# 82230KPC-1-K-1V0-241216.net
KiCad netlist of a schematic drawn in Altium Designer
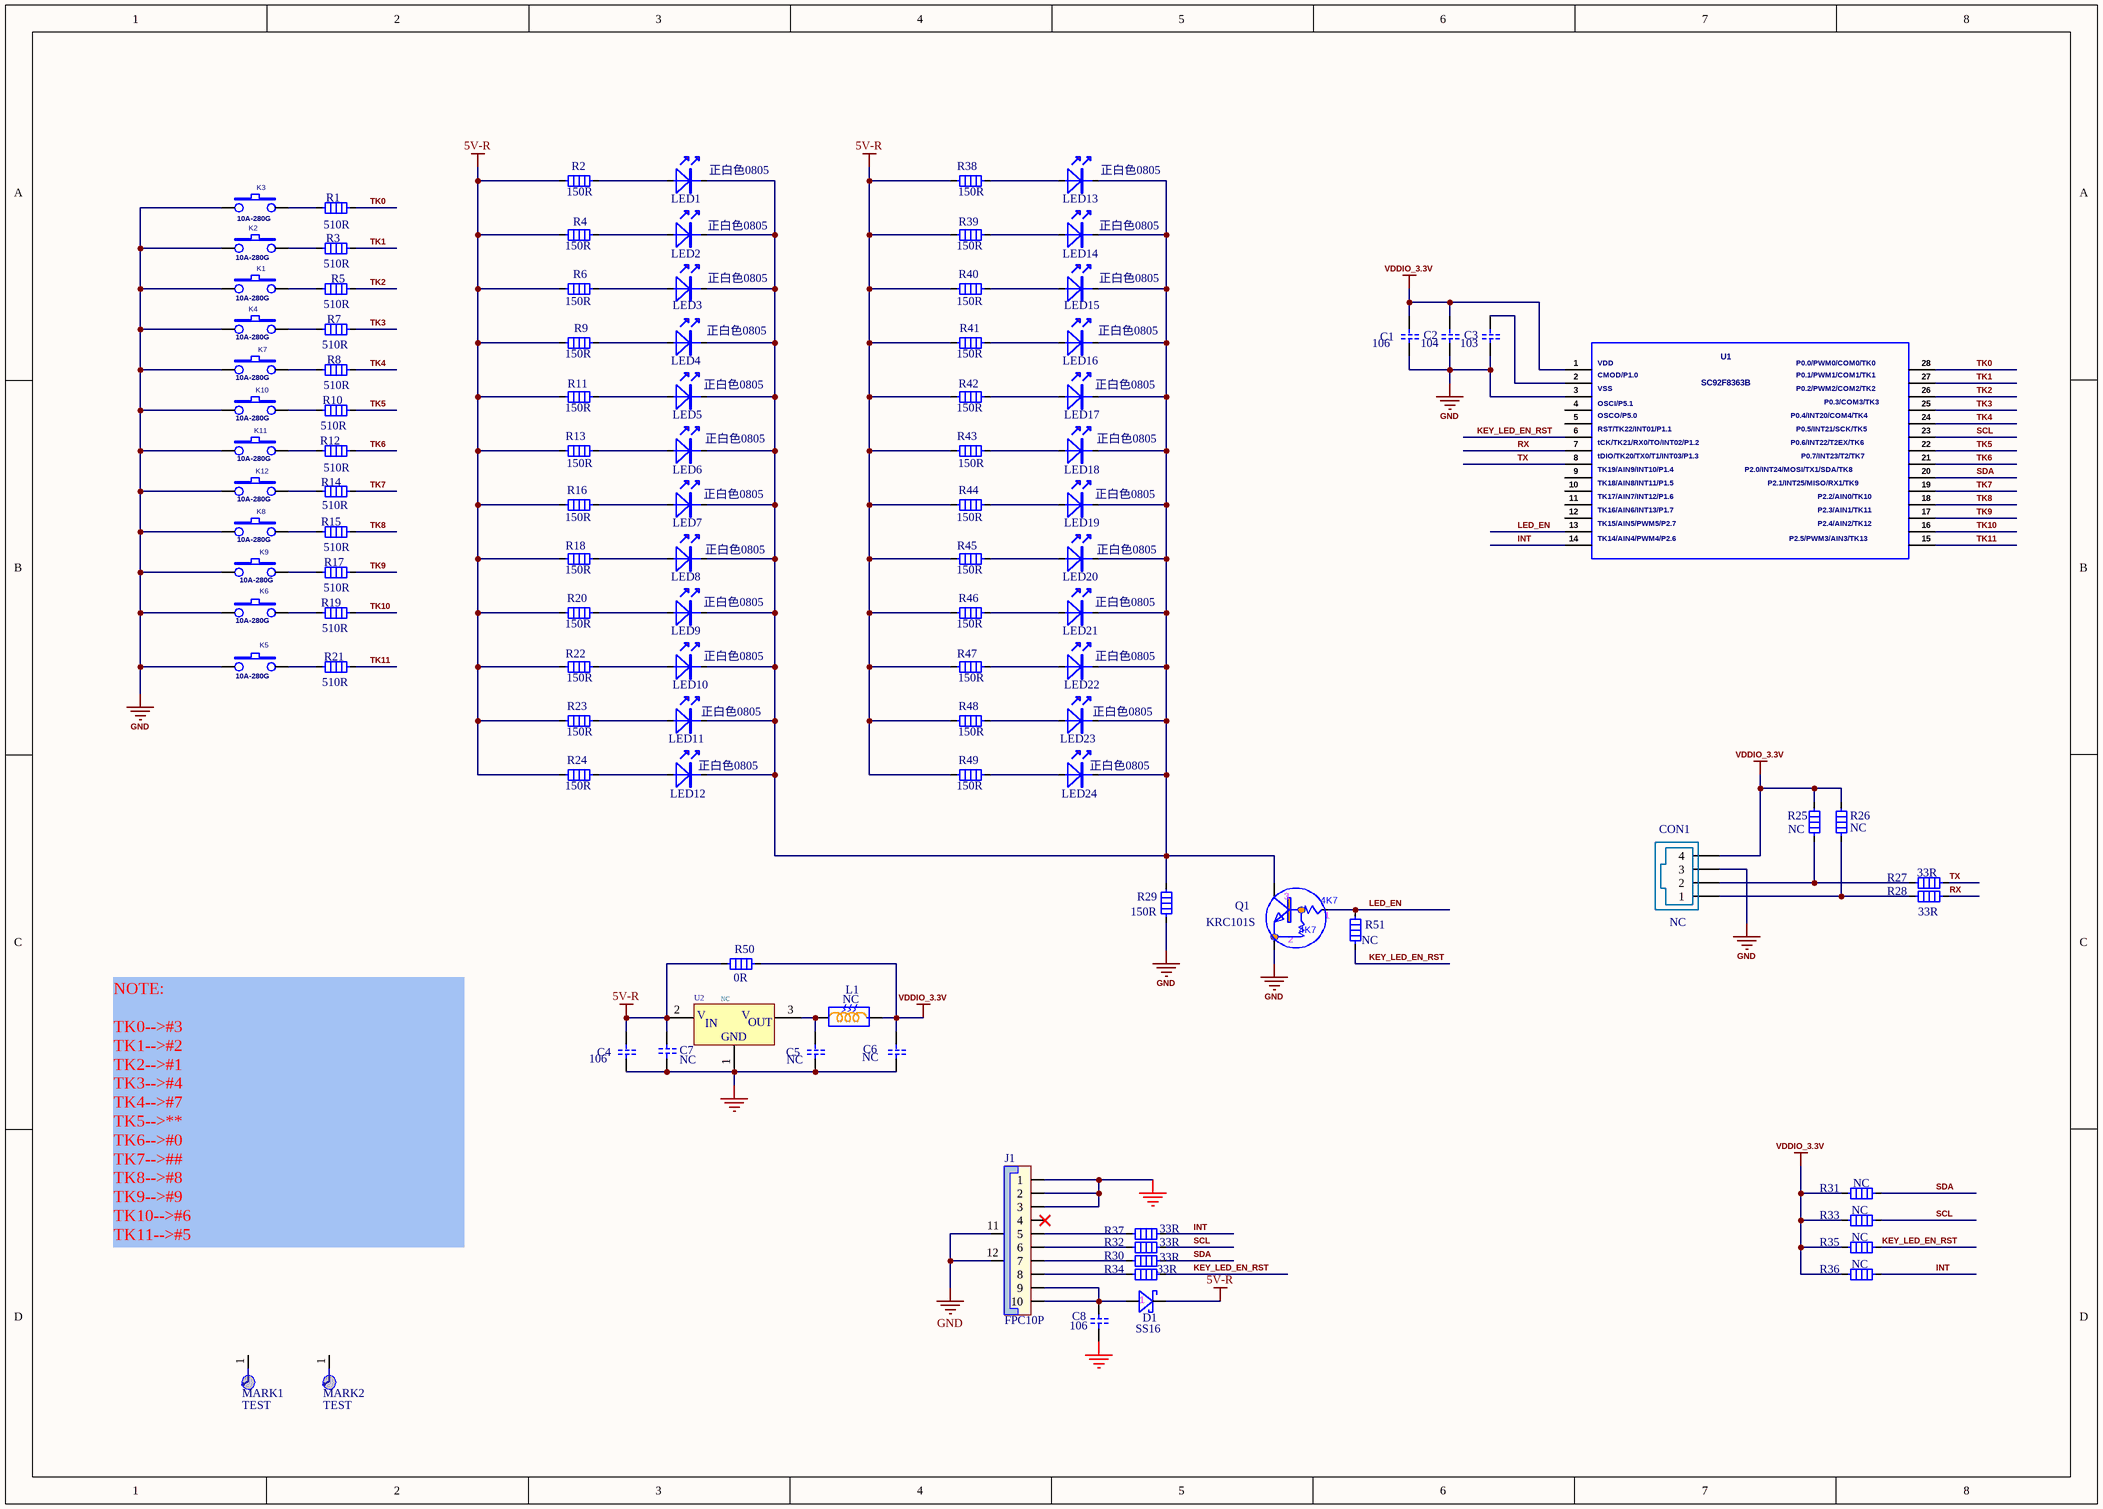
[diagram p0: 82230KPC-1-K-1V0-241216.SchDoc]

(export (version "E")
  (design (tool "Eeschema 10.0.6"))
  (components
    (comp (ref "C1")
      (value "106")
      (footprint "C0603-Z")
      (description "电容器，0603贴片，106, 6V3 精度20%")
      (libsource (lib "Dbdevice") (part "CAP_0603"))
    )
    (comp (ref "C2")
      (value "104")
      (footprint "C0603-Z")
      (description "电容器，0603贴片，104, 50V 精度10%")
      (libsource (lib "Dbdevice") (part "CAP_0603"))
    )
    (comp (ref "C3")
      (value "103")
      (footprint "C0603-Z")
      (description "电容器，0603贴片，103, 50V 精度10%")
      (libsource (lib "Dbdevice") (part "CAP_0603"))
    )
    (comp (ref "C4")
      (value "106")
      (footprint "C0603-Z")
      (description "电容器，0603贴片，106, 6V3 精度20%")
      (libsource (lib "Dbdevice") (part "CAP_0603"))
    )
    (comp (ref "C5")
      (value "NC")
      (footprint "C0603-Z")
      (description "电容器，0603贴片，106, 6V3 精度20%")
      (libsource (lib "Dbdevice") (part "CAP_0603"))
    )
    (comp (ref "C6")
      (value "NC")
      (footprint "C0603-Z")
      (description "电容器，0603贴片，106, 6V3 精度20%")
      (libsource (lib "Dbdevice") (part "CAP_0603"))
    )
    (comp (ref "C7")
      (value "NC")
      (footprint "C0603-Z")
      (description "电容器，0603贴片，104, 50V 精度10%")
      (libsource (lib "Dbdevice") (part "CAP_0603"))
    )
    (comp (ref "C8")
      (value "106")
      (footprint "C0603-Z")
      (description "电容器，0603贴片，106, 6V3 精度20%")
      (libsource (lib "Dbdevice") (part "CAP_0603"))
    )
    (comp (ref "CON1")
      (value "NC")
      (footprint "PH4P2.0_VS-Z")
      (description "4PIN直插插座（银针外露2.5mm，数据参考看上方物料图片）,4PIN插座 脚距2.0mm 插座180°米色耐高温  SCD2001AZ-104139")
      (libsource (lib "Dbdevice") (part "DIP4P"))
    )
    (comp (ref "D1")
      (value "SS16")
      (footprint "SMAF-Z")
      (description "贴片肖特基二极管，SMAF SS16（印字SS16）")
      (libsource (lib "Dbdevice") (part "DST"))
    )
    (comp (ref "J1")
      (value "FPC10P")
      (footprint "FPC10_0.5-Z")
      (description "FPC连接器 软排线插座 间距0.5mm 10P 下接触 卧贴翻盖式 (卓誉佳）（编带式）")
      (libsource (lib "Dbdevice") (part "FPC10P"))
    )
    (comp (ref "K1")
      (value "10A-280G")
      (footprint "SD-9X9-S")
      (description "锅仔片")
      (libsource (lib "*") (part "KEY_4P_SMD_6X6MM"))
    )
    (comp (ref "K2")
      (value "10A-280G")
      (footprint "SD-9X9-S")
      (description "锅仔片")
      (libsource (lib "*") (part "KEY_4P_SMD_6X6MM"))
    )
    (comp (ref "K3")
      (value "10A-280G")
      (footprint "SD-9X9-S")
      (description "锅仔片")
      (libsource (lib "*") (part "KEY_4P_SMD_6X6MM"))
    )
    (comp (ref "K4")
      (value "10A-280G")
      (footprint "SD-9X9-S")
      (description "锅仔片")
      (libsource (lib "*") (part "KEY_4P_SMD_6X6MM"))
    )
    (comp (ref "K5")
      (value "10A-280G")
      (footprint "SD-9X9-S")
      (description "锅仔片")
      (libsource (lib "*") (part "KEY_4P_SMD_6X6MM"))
    )
    (comp (ref "K6")
      (value "10A-280G")
      (footprint "SD-9X9-S")
      (description "锅仔片")
      (libsource (lib "*") (part "KEY_4P_SMD_6X6MM"))
    )
    (comp (ref "K7")
      (value "10A-280G")
      (footprint "SD-9X9-S")
      (description "锅仔片")
      (libsource (lib "*") (part "KEY_4P_SMD_6X6MM"))
    )
    (comp (ref "K8")
      (value "10A-280G")
      (footprint "SD-9X9-S")
      (description "锅仔片")
      (libsource (lib "*") (part "KEY_4P_SMD_6X6MM"))
    )
    (comp (ref "K9")
      (value "10A-280G")
      (footprint "SD-9X9-S")
      (description "锅仔片")
      (libsource (lib "*") (part "KEY_4P_SMD_6X6MM"))
    )
    (comp (ref "K10")
      (value "10A-280G")
      (footprint "SD-9X9-S")
      (description "锅仔片")
      (libsource (lib "*") (part "KEY_4P_SMD_6X6MM"))
    )
    (comp (ref "K11")
      (value "10A-280G")
      (footprint "SD-9X9-S")
      (description "锅仔片")
      (libsource (lib "*") (part "KEY_4P_SMD_6X6MM"))
    )
    (comp (ref "K12")
      (value "10A-280G")
      (footprint "SD-9X9-S")
      (description "锅仔片")
      (libsource (lib "*") (part "KEY_4P_SMD_6X6MM"))
    )
    (comp (ref "L1")
      (value "NC")
      (footprint "L0805-Z")
      (description "磁珠 0805贴片 2.5A 220ohm@100MHZ DCR=0.050")
      (libsource (lib "Dbdevice") (part "LFB"))
    )
    (comp (ref "LED1")
      (value "正白色0805")
      (footprint "LED0805AK-X")
      (description "贴片发光二极管, 0805贴片LED 正白色 发光二极管")
      (libsource (lib "Dbdevice") (part "LED_12"))
    )
    (comp (ref "LED2")
      (value "正白色0805")
      (footprint "LED0805AK-X")
      (description "贴片发光二极管, 0805贴片LED 正白色 发光二极管")
      (libsource (lib "Dbdevice") (part "LED_12"))
    )
    (comp (ref "LED3")
      (value "正白色0805")
      (footprint "LED0805AK-X")
      (description "贴片发光二极管, 0805贴片LED 正白色 发光二极管")
      (libsource (lib "Dbdevice") (part "LED_12"))
    )
    (comp (ref "LED4")
      (value "正白色0805")
      (footprint "LED0805AK-X")
      (description "贴片发光二极管, 0805贴片LED 正白色 发光二极管")
      (libsource (lib "Dbdevice") (part "LED_12"))
    )
    (comp (ref "LED5")
      (value "正白色0805")
      (footprint "LED0805AK-X")
      (description "贴片发光二极管, 0805贴片LED 正白色 发光二极管")
      (libsource (lib "Dbdevice") (part "LED_12"))
    )
    (comp (ref "LED6")
      (value "正白色0805")
      (footprint "LED0805AK-X")
      (description "贴片发光二极管, 0805贴片LED 正白色 发光二极管")
      (libsource (lib "Dbdevice") (part "LED_12"))
    )
    (comp (ref "LED7")
      (value "正白色0805")
      (footprint "LED0805AK-X")
      (description "贴片发光二极管, 0805贴片LED 正白色 发光二极管")
      (libsource (lib "Dbdevice") (part "LED_12"))
    )
    (comp (ref "LED8")
      (value "正白色0805")
      (footprint "LED0805AK-X")
      (description "贴片发光二极管, 0805贴片LED 正白色 发光二极管")
      (libsource (lib "Dbdevice") (part "LED_12"))
    )
    (comp (ref "LED9")
      (value "正白色0805")
      (footprint "LED0805AK-X")
      (description "贴片发光二极管, 0805贴片LED 正白色 发光二极管")
      (libsource (lib "Dbdevice") (part "LED_12"))
    )
    (comp (ref "LED10")
      (value "正白色0805")
      (footprint "LED0805AK-X")
      (description "贴片发光二极管, 0805贴片LED 正白色 发光二极管")
      (libsource (lib "Dbdevice") (part "LED_12"))
    )
    (comp (ref "LED11")
      (value "正白色0805")
      (footprint "LED0805AK-X")
      (description "贴片发光二极管, 0805贴片LED 正白色 发光二极管")
      (libsource (lib "Dbdevice") (part "LED_12"))
    )
    (comp (ref "LED12")
      (value "正白色0805")
      (footprint "LED0805AK-X")
      (description "贴片发光二极管, 0805贴片LED 正白色 发光二极管")
      (libsource (lib "Dbdevice") (part "LED_12"))
    )
    (comp (ref "LED13")
      (value "正白色0805")
      (footprint "LED0805AK-X")
      (description "贴片发光二极管, 0805贴片LED 正白色 发光二极管")
      (libsource (lib "Dbdevice") (part "LED_12"))
    )
    (comp (ref "LED14")
      (value "正白色0805")
      (footprint "LED0805AK-X")
      (description "贴片发光二极管, 0805贴片LED 正白色 发光二极管")
      (libsource (lib "Dbdevice") (part "LED_12"))
    )
    (comp (ref "LED15")
      (value "正白色0805")
      (footprint "LED0805AK-X")
      (description "贴片发光二极管, 0805贴片LED 正白色 发光二极管")
      (libsource (lib "Dbdevice") (part "LED_12"))
    )
    (comp (ref "LED16")
      (value "正白色0805")
      (footprint "LED0805AK-X")
      (description "贴片发光二极管, 0805贴片LED 正白色 发光二极管")
      (libsource (lib "Dbdevice") (part "LED_12"))
    )
    (comp (ref "LED17")
      (value "正白色0805")
      (footprint "LED0805AK-X")
      (description "贴片发光二极管, 0805贴片LED 正白色 发光二极管")
      (libsource (lib "Dbdevice") (part "LED_12"))
    )
    (comp (ref "LED18")
      (value "正白色0805")
      (footprint "LED0805AK-X")
      (description "贴片发光二极管, 0805贴片LED 正白色 发光二极管")
      (libsource (lib "Dbdevice") (part "LED_12"))
    )
    (comp (ref "LED19")
      (value "正白色0805")
      (footprint "LED0805AK-X")
      (description "贴片发光二极管, 0805贴片LED 正白色 发光二极管")
      (libsource (lib "Dbdevice") (part "LED_12"))
    )
    (comp (ref "LED20")
      (value "正白色0805")
      (footprint "LED0805AK-X")
      (description "贴片发光二极管, 0805贴片LED 正白色 发光二极管")
      (libsource (lib "Dbdevice") (part "LED_12"))
    )
    (comp (ref "LED21")
      (value "正白色0805")
      (footprint "LED0805AK-X")
      (description "贴片发光二极管, 0805贴片LED 正白色 发光二极管")
      (libsource (lib "Dbdevice") (part "LED_12"))
    )
    (comp (ref "LED22")
      (value "正白色0805")
      (footprint "LED0805AK-X")
      (description "贴片发光二极管, 0805贴片LED 正白色 发光二极管")
      (libsource (lib "Dbdevice") (part "LED_12"))
    )
    (comp (ref "LED23")
      (value "正白色0805")
      (footprint "LED0805AK-X")
      (description "贴片发光二极管, 0805贴片LED 正白色 发光二极管")
      (libsource (lib "Dbdevice") (part "LED_12"))
    )
    (comp (ref "LED24")
      (value "正白色0805")
      (footprint "LED0805AK-X")
      (description "贴片发光二极管, 0805贴片LED 正白色 发光二极管")
      (libsource (lib "Dbdevice") (part "LED_12"))
    )
    (comp (ref "MARK1") (value "TEST") (footprint "MARK1") (libsource (lib "*") (part "TEST")))
    (comp (ref "MARK2") (value "TEST") (footprint "MARK1") (libsource (lib "*") (part "TEST")))
    (comp (ref "Q1")
      (value "KRC101S")
      (footprint "SOT23_Z")
      (description "贴片三极管，KRC101S  SOT-23 NPN型带阻三极管")
      (libsource (lib "Dbdevice") (part "NPN_R_1"))
    )
    (comp (ref "R1")
      (value "510R")
      (footprint "R0603-Z")
      (description "电阻器，0603贴片，510R,精度5%")
      (libsource (lib "Dbdevice") (part "RES_0603"))
    )
    (comp (ref "R2")
      (value "150R")
      (footprint "R0603-Z")
      (description "电阻器，0603贴片，150R,精度5%")
      (libsource (lib "Dbdevice") (part "RES_0603"))
    )
    (comp (ref "R3")
      (value "510R")
      (footprint "R0603-Z")
      (description "电阻器，0603贴片，510R,精度5%")
      (libsource (lib "Dbdevice") (part "RES_0603"))
    )
    (comp (ref "R4")
      (value "150R")
      (footprint "R0603-Z")
      (description "电阻器，0603贴片，150R,精度5%")
      (libsource (lib "Dbdevice") (part "RES_0603"))
    )
    (comp (ref "R5")
      (value "510R")
      (footprint "R0603-Z")
      (description "电阻器，0603贴片，510R,精度5%")
      (libsource (lib "Dbdevice") (part "RES_0603"))
    )
    (comp (ref "R6")
      (value "150R")
      (footprint "R0603-Z")
      (description "电阻器，0603贴片，150R,精度5%")
      (libsource (lib "Dbdevice") (part "RES_0603"))
    )
    (comp (ref "R7")
      (value "510R")
      (footprint "R0603-Z")
      (description "电阻器，0603贴片，510R,精度5%")
      (libsource (lib "Dbdevice") (part "RES_0603"))
    )
    (comp (ref "R8")
      (value "510R")
      (footprint "R0603-Z")
      (description "电阻器，0603贴片，510R,精度5%")
      (libsource (lib "Dbdevice") (part "RES_0603"))
    )
    (comp (ref "R9")
      (value "150R")
      (footprint "R0603-Z")
      (description "电阻器，0603贴片，150R,精度5%")
      (libsource (lib "Dbdevice") (part "RES_0603"))
    )
    (comp (ref "R10")
      (value "510R")
      (footprint "R0603-Z")
      (description "电阻器，0603贴片，510R,精度5%")
      (libsource (lib "Dbdevice") (part "RES_0603"))
    )
    (comp (ref "R11")
      (value "150R")
      (footprint "R0603-Z")
      (description "电阻器，0603贴片，150R,精度5%")
      (libsource (lib "Dbdevice") (part "RES_0603"))
    )
    (comp (ref "R12")
      (value "510R")
      (footprint "R0603-Z")
      (description "电阻器，0603贴片，510R,精度5%")
      (libsource (lib "Dbdevice") (part "RES_0603"))
    )
    (comp (ref "R13")
      (value "150R")
      (footprint "R0603-Z")
      (description "电阻器，0603贴片，150R,精度5%")
      (libsource (lib "Dbdevice") (part "RES_0603"))
    )
    (comp (ref "R14")
      (value "510R")
      (footprint "R0603-Z")
      (description "电阻器，0603贴片，510R,精度5%")
      (libsource (lib "Dbdevice") (part "RES_0603"))
    )
    (comp (ref "R15")
      (value "510R")
      (footprint "R0603-Z")
      (description "电阻器，0603贴片，510R,精度5%")
      (libsource (lib "Dbdevice") (part "RES_0603"))
    )
    (comp (ref "R16")
      (value "150R")
      (footprint "R0603-Z")
      (description "电阻器，0603贴片，150R,精度5%")
      (libsource (lib "Dbdevice") (part "RES_0603"))
    )
    (comp (ref "R17")
      (value "510R")
      (footprint "R0603-Z")
      (description "电阻器，0603贴片，510R,精度5%")
      (libsource (lib "Dbdevice") (part "RES_0603"))
    )
    (comp (ref "R18")
      (value "150R")
      (footprint "R0603-Z")
      (description "电阻器，0603贴片，150R,精度5%")
      (libsource (lib "Dbdevice") (part "RES_0603"))
    )
    (comp (ref "R19")
      (value "510R")
      (footprint "R0603-Z")
      (description "电阻器，0603贴片，510R,精度5%")
      (libsource (lib "Dbdevice") (part "RES_0603"))
    )
    (comp (ref "R20")
      (value "150R")
      (footprint "R0603-Z")
      (description "电阻器，0603贴片，150R,精度5%")
      (libsource (lib "Dbdevice") (part "RES_0603"))
    )
    (comp (ref "R21")
      (value "510R")
      (footprint "R0603-Z")
      (description "电阻器，0603贴片，510R,精度5%")
      (libsource (lib "Dbdevice") (part "RES_0603"))
    )
    (comp (ref "R22")
      (value "150R")
      (footprint "R0603-Z")
      (description "电阻器，0603贴片，150R,精度5%")
      (libsource (lib "Dbdevice") (part "RES_0603"))
    )
    (comp (ref "R23")
      (value "150R")
      (footprint "R0603-Z")
      (description "电阻器，0603贴片，150R,精度5%")
      (libsource (lib "Dbdevice") (part "RES_0603"))
    )
    (comp (ref "R24")
      (value "150R")
      (footprint "R0603-Z")
      (description "电阻器，0603贴片，150R,精度5%")
      (libsource (lib "Dbdevice") (part "RES_0603"))
    )
    (comp (ref "R25")
      (value "NC")
      (footprint "R0603-Z")
      (description "电阻器，0603贴片，10K,精度5%")
      (libsource (lib "Dbdevice") (part "RES_0603"))
    )
    (comp (ref "R26")
      (value "NC")
      (footprint "R0603-Z")
      (description "电阻器，0603贴片，10K,精度5%")
      (libsource (lib "Dbdevice") (part "RES_0603"))
    )
    (comp (ref "R27")
      (value "33R")
      (footprint "R0603-Z")
      (description "电阻器，0603贴片，33R,精度5%")
      (libsource (lib "Dbdevice") (part "RES_0603"))
    )
    (comp (ref "R28")
      (value "33R")
      (footprint "R0603-Z")
      (description "电阻器，0603贴片，33R,精度5%")
      (libsource (lib "Dbdevice") (part "RES_0603"))
    )
    (comp (ref "R29")
      (value "150R")
      (footprint "R0603-Z")
      (description "电阻器，0603贴片，150R,精度5%")
      (libsource (lib "Dbdevice") (part "RES_0603"))
    )
    (comp (ref "R30")
      (value "33R")
      (footprint "R0603-Z")
      (description "电阻器，0603贴片，33R,精度5%")
      (libsource (lib "Dbdevice") (part "RES_0603"))
    )
    (comp (ref "R31")
      (value "NC")
      (footprint "R0603-Z")
      (description "电阻器，0603贴片，10K,精度5%")
      (libsource (lib "Dbdevice") (part "RES_0603"))
    )
    (comp (ref "R32")
      (value "33R")
      (footprint "R0603-Z")
      (description "电阻器，0603贴片，33R,精度5%")
      (libsource (lib "Dbdevice") (part "RES_0603"))
    )
    (comp (ref "R33")
      (value "NC")
      (footprint "R0603-Z")
      (description "电阻器，0603贴片，10K,精度5%")
      (libsource (lib "Dbdevice") (part "RES_0603"))
    )
    (comp (ref "R34")
      (value "33R")
      (footprint "R0603-Z")
      (description "电阻器，0603贴片，33R,精度5%")
      (libsource (lib "Dbdevice") (part "RES_0603"))
    )
    (comp (ref "R35")
      (value "NC")
      (footprint "R0603-Z")
      (description "电阻器，0603贴片，10K,精度5%")
      (libsource (lib "Dbdevice") (part "RES_0603"))
    )
    (comp (ref "R36")
      (value "NC")
      (footprint "R0603-Z")
      (description "电阻器，0603贴片，10K,精度5%")
      (libsource (lib "Dbdevice") (part "RES_0603"))
    )
    (comp (ref "R37")
      (value "33R")
      (footprint "R0603-Z")
      (description "电阻器，0603贴片，33R,精度5%")
      (libsource (lib "Dbdevice") (part "RES_0603"))
    )
    (comp (ref "R38")
      (value "150R")
      (footprint "R0603-Z")
      (description "电阻器，0603贴片，150R,精度5%")
      (libsource (lib "Dbdevice") (part "RES_0603"))
    )
    (comp (ref "R39")
      (value "150R")
      (footprint "R0603-Z")
      (description "电阻器，0603贴片，150R,精度5%")
      (libsource (lib "Dbdevice") (part "RES_0603"))
    )
    (comp (ref "R40")
      (value "150R")
      (footprint "R0603-Z")
      (description "电阻器，0603贴片，150R,精度5%")
      (libsource (lib "Dbdevice") (part "RES_0603"))
    )
    (comp (ref "R41")
      (value "150R")
      (footprint "R0603-Z")
      (description "电阻器，0603贴片，150R,精度5%")
      (libsource (lib "Dbdevice") (part "RES_0603"))
    )
    (comp (ref "R42")
      (value "150R")
      (footprint "R0603-Z")
      (description "电阻器，0603贴片，150R,精度5%")
      (libsource (lib "Dbdevice") (part "RES_0603"))
    )
    (comp (ref "R43")
      (value "150R")
      (footprint "R0603-Z")
      (description "电阻器，0603贴片，150R,精度5%")
      (libsource (lib "Dbdevice") (part "RES_0603"))
    )
    (comp (ref "R44")
      (value "150R")
      (footprint "R0603-Z")
      (description "电阻器，0603贴片，150R,精度5%")
      (libsource (lib "Dbdevice") (part "RES_0603"))
    )
    (comp (ref "R45")
      (value "150R")
      (footprint "R0603-Z")
      (description "电阻器，0603贴片，150R,精度5%")
      (libsource (lib "Dbdevice") (part "RES_0603"))
    )
    (comp (ref "R46")
      (value "150R")
      (footprint "R0603-Z")
      (description "电阻器，0603贴片，150R,精度5%")
      (libsource (lib "Dbdevice") (part "RES_0603"))
    )
    (comp (ref "R47")
      (value "150R")
      (footprint "R0603-Z")
      (description "电阻器，0603贴片，150R,精度5%")
      (libsource (lib "Dbdevice") (part "RES_0603"))
    )
    (comp (ref "R48")
      (value "150R")
      (footprint "R0603-Z")
      (description "电阻器，0603贴片，150R,精度5%")
      (libsource (lib "Dbdevice") (part "RES_0603"))
    )
    (comp (ref "R49")
      (value "150R")
      (footprint "R0603-Z")
      (description "电阻器，0603贴片，150R,精度5%")
      (libsource (lib "Dbdevice") (part "RES_0603"))
    )
    (comp (ref "R50")
      (value "0R")
      (footprint "R0603-Z")
      (description "电阻器，0603贴片，0R,精度5%")
      (libsource (lib "Dbdevice") (part "RES_0603"))
    )
    (comp (ref "R51")
      (value "NC")
      (footprint "R0603-Z")
      (description "电阻器，0603贴片，0R,精度5%")
      (libsource (lib "Dbdevice") (part "RES_0603"))
    )
    (comp (ref "U1") (value "SC92F8363B") (footprint "SSOP28-Z") (libsource (lib "*") (part "SC92F8363B")))
    (comp (ref "U2")
      (value "NC")
      (footprint "SOT-89-Z")
      (description "三端稳压器，三端稳压器HT7533 电流100mA SOT-89")
      (libsource (lib "*") (part "7905"))
    )
  )
  (nets
    (net (code "1") (name "/INT") (class "Default")
      (node (ref "R36") (pin "1") (pintype "passive"))
      (node (ref "R37") (pin "1") (pintype "passive"))
      (node (ref "U1") (pin "14") (pinfunction "14_14") (pintype "passive"))
    )
    (net (code "2") (name "/KEY_LED_EN_RST") (class "Default")
      (node (ref "R34") (pin "1") (pintype "passive"))
      (node (ref "R35") (pin "1") (pintype "passive"))
      (node (ref "R51") (pin "1") (pintype "passive"))
      (node (ref "U1") (pin "6") (pinfunction "6_6") (pintype "passive"))
    )
    (net (code "3") (name "/LED_EN") (class "Default")
      (node (ref "Q1") (pin "1") (pinfunction "B_1") (pintype "passive"))
      (node (ref "R51") (pin "2") (pintype "passive"))
      (node (ref "U1") (pin "13") (pinfunction "13_13") (pintype "passive"))
    )
    (net (code "4") (name "/RX") (class "Default")
      (node (ref "R28") (pin "1") (pintype "passive"))
      (node (ref "U1") (pin "7") (pinfunction "7_7") (pintype "passive"))
    )
    (net (code "5") (name "/SCL") (class "Default")
      (node (ref "R32") (pin "1") (pintype "passive"))
      (node (ref "R33") (pin "1") (pintype "passive"))
      (node (ref "U1") (pin "23") (pinfunction "23_23") (pintype "passive"))
    )
    (net (code "6") (name "/SDA") (class "Default")
      (node (ref "R30") (pin "1") (pintype "passive"))
      (node (ref "R31") (pin "1") (pintype "passive"))
      (node (ref "U1") (pin "20") (pinfunction "20_20") (pintype "passive"))
    )
    (net (code "7") (name "/TK0") (class "Default")
      (node (ref "R1") (pin "1") (pintype "passive"))
      (node (ref "U1") (pin "28") (pinfunction "28_28") (pintype "passive"))
    )
    (net (code "8") (name "/TK1") (class "Default")
      (node (ref "R3") (pin "1") (pintype "passive"))
      (node (ref "U1") (pin "27") (pinfunction "27_27") (pintype "passive"))
    )
    (net (code "9") (name "/TK2") (class "Default")
      (node (ref "R5") (pin "1") (pintype "passive"))
      (node (ref "U1") (pin "26") (pinfunction "26_26") (pintype "passive"))
    )
    (net (code "10") (name "/TK3") (class "Default")
      (node (ref "R7") (pin "1") (pintype "passive"))
      (node (ref "U1") (pin "25") (pinfunction "25_25") (pintype "passive"))
    )
    (net (code "11") (name "/TK4") (class "Default")
      (node (ref "R8") (pin "1") (pintype "passive"))
      (node (ref "U1") (pin "24") (pinfunction "24_24") (pintype "passive"))
    )
    (net (code "12") (name "/TK5") (class "Default")
      (node (ref "R10") (pin "1") (pintype "passive"))
      (node (ref "U1") (pin "22") (pinfunction "22_22") (pintype "passive"))
    )
    (net (code "13") (name "/TK6") (class "Default")
      (node (ref "R12") (pin "1") (pintype "passive"))
      (node (ref "U1") (pin "21") (pinfunction "21_21") (pintype "passive"))
    )
    (net (code "14") (name "/TK7") (class "Default")
      (node (ref "R14") (pin "1") (pintype "passive"))
      (node (ref "U1") (pin "19") (pinfunction "19_19") (pintype "passive"))
    )
    (net (code "15") (name "/TK8") (class "Default")
      (node (ref "R15") (pin "1") (pintype "passive"))
      (node (ref "U1") (pin "18") (pinfunction "18_18") (pintype "passive"))
    )
    (net (code "16") (name "/TK9") (class "Default")
      (node (ref "R17") (pin "1") (pintype "passive"))
      (node (ref "U1") (pin "17") (pinfunction "17_17") (pintype "passive"))
    )
    (net (code "17") (name "/TK10") (class "Default")
      (node (ref "R19") (pin "1") (pintype "passive"))
      (node (ref "U1") (pin "16") (pinfunction "16_16") (pintype "passive"))
    )
    (net (code "18") (name "/TK11") (class "Default")
      (node (ref "R21") (pin "1") (pintype "passive"))
      (node (ref "U1") (pin "15") (pinfunction "15_15") (pintype "passive"))
    )
    (net (code "19") (name "/TX") (class "Default")
      (node (ref "R27") (pin "1") (pintype "passive"))
      (node (ref "U1") (pin "8") (pinfunction "8_8") (pintype "passive"))
    )
    (net (code "20") (name "5V-R") (class "Default")
      (node (ref "C4") (pin "1") (pinfunction "1_1") (pintype "passive"))
      (node (ref "C7") (pin "2") (pinfunction "2_2") (pintype "passive"))
      (node (ref "D1") (pin "2") (pinfunction "K_2") (pintype "passive"))
      (node (ref "R11") (pin "2") (pintype "passive"))
      (node (ref "R13") (pin "2") (pintype "passive"))
      (node (ref "R16") (pin "2") (pintype "passive"))
      (node (ref "R18") (pin "2") (pintype "passive"))
      (node (ref "R2") (pin "2") (pintype "passive"))
      (node (ref "R20") (pin "2") (pintype "passive"))
      (node (ref "R22") (pin "2") (pintype "passive"))
      (node (ref "R23") (pin "2") (pintype "passive"))
      (node (ref "R24") (pin "2") (pintype "passive"))
      (node (ref "R38") (pin "2") (pintype "passive"))
      (node (ref "R39") (pin "2") (pintype "passive"))
      (node (ref "R4") (pin "2") (pintype "passive"))
      (node (ref "R40") (pin "2") (pintype "passive"))
      (node (ref "R41") (pin "2") (pintype "passive"))
      (node (ref "R42") (pin "2") (pintype "passive"))
      (node (ref "R43") (pin "2") (pintype "passive"))
      (node (ref "R44") (pin "2") (pintype "passive"))
      (node (ref "R45") (pin "2") (pintype "passive"))
      (node (ref "R46") (pin "2") (pintype "passive"))
      (node (ref "R47") (pin "2") (pintype "passive"))
      (node (ref "R48") (pin "2") (pintype "passive"))
      (node (ref "R49") (pin "2") (pintype "passive"))
      (node (ref "R50") (pin "1") (pintype "passive"))
      (node (ref "R6") (pin "2") (pintype "passive"))
      (node (ref "R9") (pin "2") (pintype "passive"))
      (node (ref "U2") (pin "2") (pinfunction "VIN_2") (pintype "passive"))
    )
    (net (code "21") (name "GND") (class "Default")
      (node (ref "C1") (pin "2") (pinfunction "2_2") (pintype "passive"))
      (node (ref "C2") (pin "2") (pinfunction "2_2") (pintype "passive"))
      (node (ref "C3") (pin "2") (pinfunction "2_2") (pintype "passive"))
      (node (ref "C4") (pin "2") (pinfunction "2_2") (pintype "passive"))
      (node (ref "C5") (pin "2") (pinfunction "2_2") (pintype "passive"))
      (node (ref "C6") (pin "2") (pinfunction "2_2") (pintype "passive"))
      (node (ref "C7") (pin "1") (pinfunction "1_1") (pintype "passive"))
      (node (ref "C8") (pin "1") (pinfunction "1_1") (pintype "passive"))
      (node (ref "CON1") (pin "3") (pinfunction "3_3") (pintype "passive"))
      (node (ref "J1") (pin "1") (pinfunction "1_1") (pintype "passive"))
      (node (ref "J1") (pin "11") (pinfunction "11_11") (pintype "passive"))
      (node (ref "J1") (pin "12") (pinfunction "12_12") (pintype "passive"))
      (node (ref "J1") (pin "2") (pinfunction "2_2") (pintype "passive"))
      (node (ref "J1") (pin "3") (pinfunction "3_3") (pintype "passive"))
      (node (ref "K1") (pin "2") (pinfunction "2_2") (pintype "passive"))
      (node (ref "K10") (pin "2") (pinfunction "2_2") (pintype "passive"))
      (node (ref "K11") (pin "2") (pinfunction "2_2") (pintype "passive"))
      (node (ref "K12") (pin "2") (pinfunction "2_2") (pintype "passive"))
      (node (ref "K2") (pin "2") (pinfunction "2_2") (pintype "passive"))
      (node (ref "K3") (pin "2") (pinfunction "2_2") (pintype "passive"))
      (node (ref "K4") (pin "2") (pinfunction "2_2") (pintype "passive"))
      (node (ref "K5") (pin "2") (pinfunction "2_2") (pintype "passive"))
      (node (ref "K6") (pin "2") (pinfunction "2_2") (pintype "passive"))
      (node (ref "K7") (pin "2") (pinfunction "2_2") (pintype "passive"))
      (node (ref "K8") (pin "2") (pinfunction "2_2") (pintype "passive"))
      (node (ref "K9") (pin "2") (pinfunction "2_2") (pintype "passive"))
      (node (ref "Q1") (pin "2") (pinfunction "E_2") (pintype "passive"))
      (node (ref "R29") (pin "2") (pintype "passive"))
      (node (ref "U1") (pin "3") (pinfunction "3_3") (pintype "passive"))
      (node (ref "U2") (pin "1") (pinfunction "GND_1") (pintype "passive"))
    )
    (net (code "22") (name "Net-(C3-Pad1)") (class "Default")
      (node (ref "C3") (pin "1") (pinfunction "1_1") (pintype "passive"))
      (node (ref "U1") (pin "2") (pinfunction "2_2") (pintype "passive"))
    )
    (net (code "23") (name "Net-(CON1-Pad1)") (class "Default")
      (node (ref "CON1") (pin "1") (pinfunction "1_1") (pintype "passive"))
      (node (ref "R26") (pin "2") (pintype "passive"))
      (node (ref "R28") (pin "2") (pintype "passive"))
    )
    (net (code "24") (name "Net-(CON1-Pad2)") (class "Default")
      (node (ref "CON1") (pin "2") (pinfunction "2_2") (pintype "passive"))
      (node (ref "R25") (pin "2") (pintype "passive"))
      (node (ref "R27") (pin "2") (pintype "passive"))
    )
    (net (code "25") (name "Net-(D1-A)") (class "Default")
      (node (ref "C8") (pin "2") (pinfunction "2_2") (pintype "passive"))
      (node (ref "D1") (pin "1") (pinfunction "A_1") (pintype "passive"))
      (node (ref "J1") (pin "10") (pinfunction "10_10") (pintype "passive"))
      (node (ref "J1") (pin "9") (pinfunction "9_9") (pintype "passive"))
    )
    (net (code "26") (name "Net-(J1-Pad5)") (class "Default")
      (node (ref "J1") (pin "5") (pinfunction "5_5") (pintype "passive"))
      (node (ref "R37") (pin "2") (pintype "passive"))
    )
    (net (code "27") (name "Net-(J1-Pad6)") (class "Default")
      (node (ref "J1") (pin "6") (pinfunction "6_6") (pintype "passive"))
      (node (ref "R32") (pin "2") (pintype "passive"))
    )
    (net (code "28") (name "Net-(J1-Pad7)") (class "Default")
      (node (ref "J1") (pin "7") (pinfunction "7_7") (pintype "passive"))
      (node (ref "R30") (pin "2") (pintype "passive"))
    )
    (net (code "29") (name "Net-(J1-Pad8)") (class "Default")
      (node (ref "J1") (pin "8") (pinfunction "8_8") (pintype "passive"))
      (node (ref "R34") (pin "2") (pintype "passive"))
    )
    (net (code "30") (name "Net-(K1-Pad1)") (class "Default")
      (node (ref "K1") (pin "1") (pinfunction "1_1") (pintype "passive"))
      (node (ref "R5") (pin "2") (pintype "passive"))
    )
    (net (code "31") (name "Net-(K2-Pad1)") (class "Default")
      (node (ref "K2") (pin "1") (pinfunction "1_1") (pintype "passive"))
      (node (ref "R3") (pin "2") (pintype "passive"))
    )
    (net (code "32") (name "Net-(K3-Pad1)") (class "Default")
      (node (ref "K3") (pin "1") (pinfunction "1_1") (pintype "passive"))
      (node (ref "R1") (pin "2") (pintype "passive"))
    )
    (net (code "33") (name "Net-(K4-Pad1)") (class "Default")
      (node (ref "K4") (pin "1") (pinfunction "1_1") (pintype "passive"))
      (node (ref "R7") (pin "2") (pintype "passive"))
    )
    (net (code "34") (name "Net-(K5-Pad1)") (class "Default")
      (node (ref "K5") (pin "1") (pinfunction "1_1") (pintype "passive"))
      (node (ref "R21") (pin "2") (pintype "passive"))
    )
    (net (code "35") (name "Net-(K6-Pad1)") (class "Default")
      (node (ref "K6") (pin "1") (pinfunction "1_1") (pintype "passive"))
      (node (ref "R19") (pin "2") (pintype "passive"))
    )
    (net (code "36") (name "Net-(K7-Pad1)") (class "Default")
      (node (ref "K7") (pin "1") (pinfunction "1_1") (pintype "passive"))
      (node (ref "R8") (pin "2") (pintype "passive"))
    )
    (net (code "37") (name "Net-(K8-Pad1)") (class "Default")
      (node (ref "K8") (pin "1") (pinfunction "1_1") (pintype "passive"))
      (node (ref "R15") (pin "2") (pintype "passive"))
    )
    (net (code "38") (name "Net-(K9-Pad1)") (class "Default")
      (node (ref "K9") (pin "1") (pinfunction "1_1") (pintype "passive"))
      (node (ref "R17") (pin "2") (pintype "passive"))
    )
    (net (code "39") (name "Net-(K10-Pad1)") (class "Default")
      (node (ref "K10") (pin "1") (pinfunction "1_1") (pintype "passive"))
      (node (ref "R10") (pin "2") (pintype "passive"))
    )
    (net (code "40") (name "Net-(K11-Pad1)") (class "Default")
      (node (ref "K11") (pin "1") (pinfunction "1_1") (pintype "passive"))
      (node (ref "R12") (pin "2") (pintype "passive"))
    )
    (net (code "41") (name "Net-(K12-Pad1)") (class "Default")
      (node (ref "K12") (pin "1") (pinfunction "1_1") (pintype "passive"))
      (node (ref "R14") (pin "2") (pintype "passive"))
    )
    (net (code "42") (name "Net-(LED1-Pad1)") (class "Default")
      (node (ref "LED1") (pin "1") (pinfunction "1_1") (pintype "passive"))
      (node (ref "R2") (pin "1") (pintype "passive"))
    )
    (net (code "43") (name "Net-(LED2-Pad1)") (class "Default")
      (node (ref "LED2") (pin "1") (pinfunction "1_1") (pintype "passive"))
      (node (ref "R4") (pin "1") (pintype "passive"))
    )
    (net (code "44") (name "Net-(LED3-Pad1)") (class "Default")
      (node (ref "LED3") (pin "1") (pinfunction "1_1") (pintype "passive"))
      (node (ref "R6") (pin "1") (pintype "passive"))
    )
    (net (code "45") (name "Net-(LED4-Pad1)") (class "Default")
      (node (ref "LED4") (pin "1") (pinfunction "1_1") (pintype "passive"))
      (node (ref "R9") (pin "1") (pintype "passive"))
    )
    (net (code "46") (name "Net-(LED5-Pad1)") (class "Default")
      (node (ref "LED5") (pin "1") (pinfunction "1_1") (pintype "passive"))
      (node (ref "R11") (pin "1") (pintype "passive"))
    )
    (net (code "47") (name "Net-(LED6-Pad1)") (class "Default")
      (node (ref "LED6") (pin "1") (pinfunction "1_1") (pintype "passive"))
      (node (ref "R13") (pin "1") (pintype "passive"))
    )
    (net (code "48") (name "Net-(LED7-Pad1)") (class "Default")
      (node (ref "LED7") (pin "1") (pinfunction "1_1") (pintype "passive"))
      (node (ref "R16") (pin "1") (pintype "passive"))
    )
    (net (code "49") (name "Net-(LED8-Pad1)") (class "Default")
      (node (ref "LED8") (pin "1") (pinfunction "1_1") (pintype "passive"))
      (node (ref "R18") (pin "1") (pintype "passive"))
    )
    (net (code "50") (name "Net-(LED9-Pad1)") (class "Default")
      (node (ref "LED9") (pin "1") (pinfunction "1_1") (pintype "passive"))
      (node (ref "R20") (pin "1") (pintype "passive"))
    )
    (net (code "51") (name "Net-(LED10-Pad1)") (class "Default")
      (node (ref "LED10") (pin "1") (pinfunction "1_1") (pintype "passive"))
      (node (ref "R22") (pin "1") (pintype "passive"))
    )
    (net (code "52") (name "Net-(LED11-Pad1)") (class "Default")
      (node (ref "LED11") (pin "1") (pinfunction "1_1") (pintype "passive"))
      (node (ref "R23") (pin "1") (pintype "passive"))
    )
    (net (code "53") (name "Net-(LED12-Pad1)") (class "Default")
      (node (ref "LED12") (pin "1") (pinfunction "1_1") (pintype "passive"))
      (node (ref "R24") (pin "1") (pintype "passive"))
    )
    (net (code "54") (name "Net-(LED13-Pad1)") (class "Default")
      (node (ref "LED13") (pin "1") (pinfunction "1_1") (pintype "passive"))
      (node (ref "R38") (pin "1") (pintype "passive"))
    )
    (net (code "55") (name "Net-(LED14-Pad1)") (class "Default")
      (node (ref "LED14") (pin "1") (pinfunction "1_1") (pintype "passive"))
      (node (ref "R39") (pin "1") (pintype "passive"))
    )
    (net (code "56") (name "Net-(LED15-Pad1)") (class "Default")
      (node (ref "LED15") (pin "1") (pinfunction "1_1") (pintype "passive"))
      (node (ref "R40") (pin "1") (pintype "passive"))
    )
    (net (code "57") (name "Net-(LED16-Pad1)") (class "Default")
      (node (ref "LED16") (pin "1") (pinfunction "1_1") (pintype "passive"))
      (node (ref "R41") (pin "1") (pintype "passive"))
    )
    (net (code "58") (name "Net-(LED17-Pad1)") (class "Default")
      (node (ref "LED17") (pin "1") (pinfunction "1_1") (pintype "passive"))
      (node (ref "R42") (pin "1") (pintype "passive"))
    )
    (net (code "59") (name "Net-(LED18-Pad1)") (class "Default")
      (node (ref "LED18") (pin "1") (pinfunction "1_1") (pintype "passive"))
      (node (ref "R43") (pin "1") (pintype "passive"))
    )
    (net (code "60") (name "Net-(LED19-Pad1)") (class "Default")
      (node (ref "LED19") (pin "1") (pinfunction "1_1") (pintype "passive"))
      (node (ref "R44") (pin "1") (pintype "passive"))
    )
    (net (code "61") (name "Net-(LED20-Pad1)") (class "Default")
      (node (ref "LED20") (pin "1") (pinfunction "1_1") (pintype "passive"))
      (node (ref "R45") (pin "1") (pintype "passive"))
    )
    (net (code "62") (name "Net-(LED21-Pad1)") (class "Default")
      (node (ref "LED21") (pin "1") (pinfunction "1_1") (pintype "passive"))
      (node (ref "R46") (pin "1") (pintype "passive"))
    )
    (net (code "63") (name "Net-(LED22-Pad1)") (class "Default")
      (node (ref "LED22") (pin "1") (pinfunction "1_1") (pintype "passive"))
      (node (ref "R47") (pin "1") (pintype "passive"))
    )
    (net (code "64") (name "Net-(LED23-Pad1)") (class "Default")
      (node (ref "LED23") (pin "1") (pinfunction "1_1") (pintype "passive"))
      (node (ref "R48") (pin "1") (pintype "passive"))
    )
    (net (code "65") (name "Net-(LED24-Pad1)") (class "Default")
      (node (ref "LED24") (pin "1") (pinfunction "1_1") (pintype "passive"))
      (node (ref "R49") (pin "1") (pintype "passive"))
    )
    (net (code "66") (name "Net-(Q1-C)") (class "Default")
      (node (ref "LED1") (pin "2") (pinfunction "2_2") (pintype "passive"))
      (node (ref "LED10") (pin "2") (pinfunction "2_2") (pintype "passive"))
      (node (ref "LED11") (pin "2") (pinfunction "2_2") (pintype "passive"))
      (node (ref "LED12") (pin "2") (pinfunction "2_2") (pintype "passive"))
      (node (ref "LED13") (pin "2") (pinfunction "2_2") (pintype "passive"))
      (node (ref "LED14") (pin "2") (pinfunction "2_2") (pintype "passive"))
      (node (ref "LED15") (pin "2") (pinfunction "2_2") (pintype "passive"))
      (node (ref "LED16") (pin "2") (pinfunction "2_2") (pintype "passive"))
      (node (ref "LED17") (pin "2") (pinfunction "2_2") (pintype "passive"))
      (node (ref "LED18") (pin "2") (pinfunction "2_2") (pintype "passive"))
      (node (ref "LED19") (pin "2") (pinfunction "2_2") (pintype "passive"))
      (node (ref "LED2") (pin "2") (pinfunction "2_2") (pintype "passive"))
      (node (ref "LED20") (pin "2") (pinfunction "2_2") (pintype "passive"))
      (node (ref "LED21") (pin "2") (pinfunction "2_2") (pintype "passive"))
      (node (ref "LED22") (pin "2") (pinfunction "2_2") (pintype "passive"))
      (node (ref "LED23") (pin "2") (pinfunction "2_2") (pintype "passive"))
      (node (ref "LED24") (pin "2") (pinfunction "2_2") (pintype "passive"))
      (node (ref "LED3") (pin "2") (pinfunction "2_2") (pintype "passive"))
      (node (ref "LED4") (pin "2") (pinfunction "2_2") (pintype "passive"))
      (node (ref "LED5") (pin "2") (pinfunction "2_2") (pintype "passive"))
      (node (ref "LED6") (pin "2") (pinfunction "2_2") (pintype "passive"))
      (node (ref "LED7") (pin "2") (pinfunction "2_2") (pintype "passive"))
      (node (ref "LED8") (pin "2") (pinfunction "2_2") (pintype "passive"))
      (node (ref "LED9") (pin "2") (pinfunction "2_2") (pintype "passive"))
      (node (ref "Q1") (pin "3") (pinfunction "C_3") (pintype "passive"))
      (node (ref "R29") (pin "1") (pintype "passive"))
    )
    (net (code "67") (name "Net-(U2-VOUT)") (class "Default")
      (node (ref "C5") (pin "1") (pinfunction "1_1") (pintype "passive"))
      (node (ref "L1") (pin "1") (pinfunction "1_1") (pintype "passive"))
      (node (ref "U2") (pin "3") (pinfunction "VOUT_3") (pintype "passive"))
    )
    (net (code "68") (name "VDDIO_3.3V") (class "Default")
      (node (ref "C1") (pin "1") (pinfunction "1_1") (pintype "passive"))
      (node (ref "C2") (pin "1") (pinfunction "1_1") (pintype "passive"))
      (node (ref "C6") (pin "1") (pinfunction "1_1") (pintype "passive"))
      (node (ref "CON1") (pin "4") (pinfunction "4_4") (pintype "passive"))
      (node (ref "L1") (pin "2") (pinfunction "2_2") (pintype "passive"))
      (node (ref "R25") (pin "1") (pintype "passive"))
      (node (ref "R26") (pin "1") (pintype "passive"))
      (node (ref "R31") (pin "2") (pintype "passive"))
      (node (ref "R33") (pin "2") (pintype "passive"))
      (node (ref "R35") (pin "2") (pintype "passive"))
      (node (ref "R36") (pin "2") (pintype "passive"))
      (node (ref "R50") (pin "2") (pintype "passive"))
      (node (ref "U1") (pin "1") (pinfunction "1_1") (pintype "passive"))
    )
    (net (code "69") (name "unconnected-(J1-Pad4)") (class "Default")
      (node (ref "J1") (pin "4") (pinfunction "4_4") (pintype "passive+no_connect"))
    )
    (net (code "70") (name "unconnected-(MARK1-Pad1)") (class "Default")
      (node (ref "MARK1") (pin "1") (pintype "passive"))
    )
    (net (code "71") (name "unconnected-(MARK2-Pad1)") (class "Default")
      (node (ref "MARK2") (pin "1") (pintype "passive"))
    )
    (net (code "72") (name "unconnected-(U1-Pad4)") (class "Default")
      (node (ref "U1") (pin "4") (pinfunction "4_4") (pintype "passive"))
    )
    (net (code "73") (name "unconnected-(U1-Pad5)") (class "Default")
      (node (ref "U1") (pin "5") (pinfunction "5_5") (pintype "passive"))
    )
    (net (code "74") (name "unconnected-(U1-Pad9)") (class "Default")
      (node (ref "U1") (pin "9") (pinfunction "9_9") (pintype "passive"))
    )
    (net (code "75") (name "unconnected-(U1-Pad10)") (class "Default")
      (node (ref "U1") (pin "10") (pinfunction "10_10") (pintype "passive"))
    )
    (net (code "76") (name "unconnected-(U1-Pad11)") (class "Default")
      (node (ref "U1") (pin "11") (pinfunction "11_11") (pintype "passive"))
    )
    (net (code "77") (name "unconnected-(U1-Pad12)") (class "Default")
      (node (ref "U1") (pin "12") (pinfunction "12_12") (pintype "passive"))
    )
  )
)
